# emg-bridge.net
KiCad netlist of a schematic drawn in EAGLE
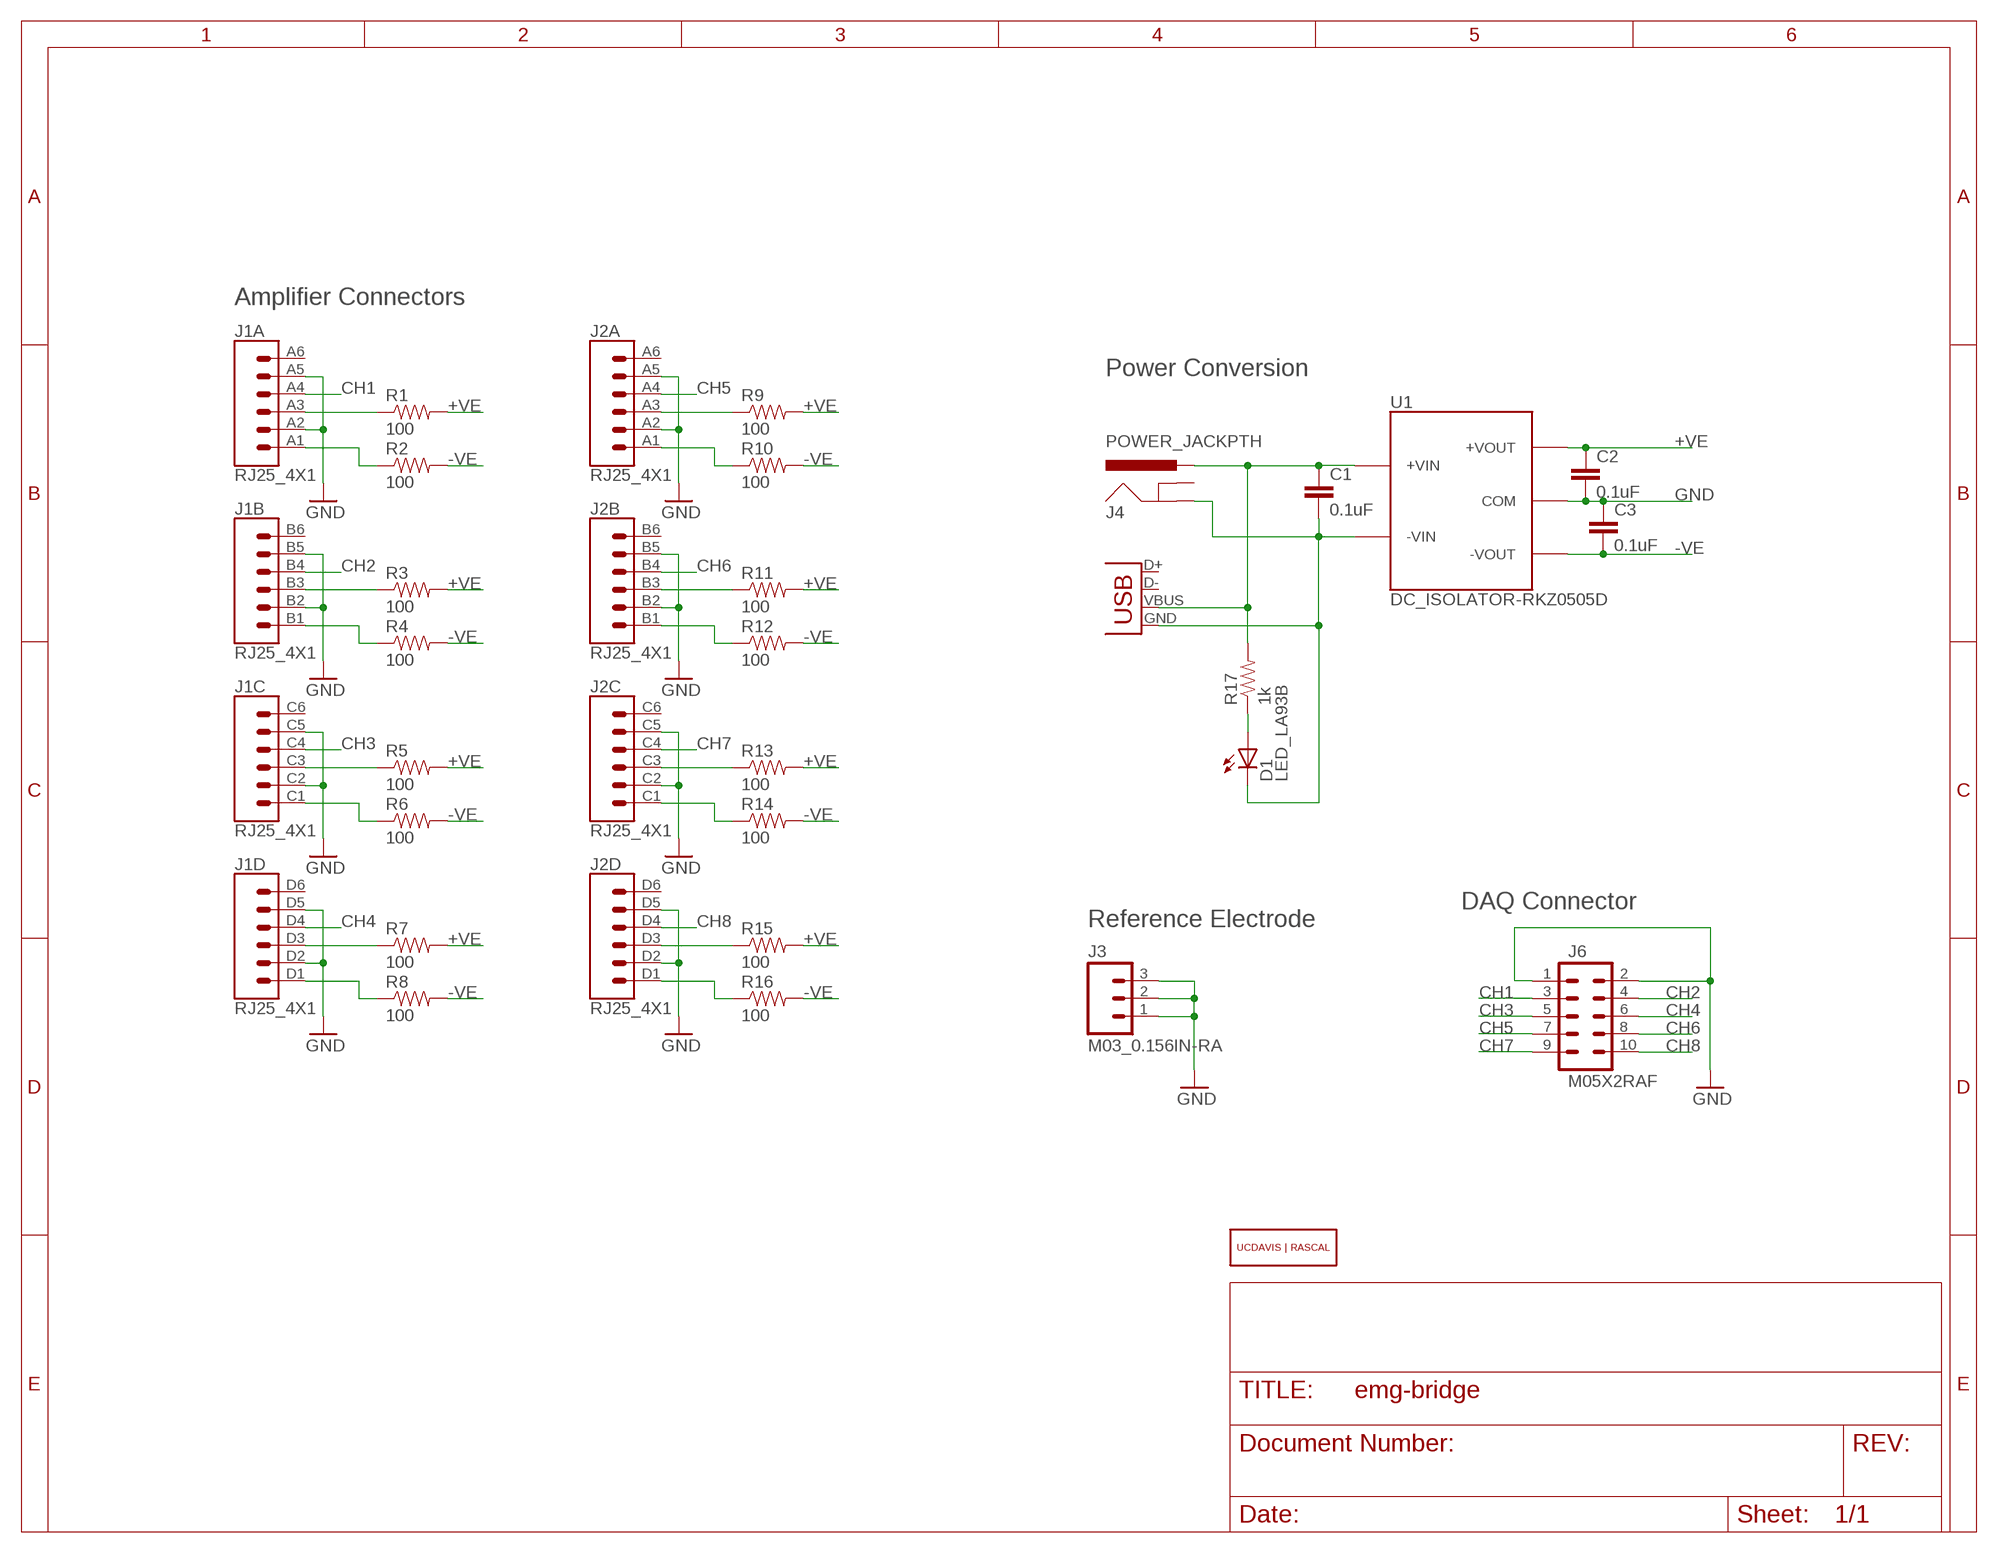
[diagram p0: schematic, sheet 1]

(export (version "E")
  (design (tool "Eeschema 10.0.6"))
  (components
    (comp (ref "C1")
      (value "0.1uF")
      (footprint "eagle-import:0805")
      (libsource (lib "eagle-import") (part "CAP0805"))
    )
    (comp (ref "C2")
      (value "0.1uF")
      (footprint "eagle-import:0805")
      (libsource (lib "eagle-import") (part "CAP0805"))
    )
    (comp (ref "C3")
      (value "0.1uF")
      (footprint "eagle-import:0805")
      (libsource (lib "eagle-import") (part "CAP0805"))
    )
    (comp (ref "D1")
      (value "LED_LA93B")
      (footprint "eagle-import:LED_RA")
      (libsource (lib "eagle-import") (part "LED_LA93B"))
    )
    (comp (ref "J1")
      (value "RJ25_4X1")
      (footprint "eagle-import:RJ25_4X1")
      (libsource (lib "eagle-import") (part "RJ25_4X1"))
    )
    (comp (ref "J2")
      (value "RJ25_4X1")
      (footprint "eagle-import:RJ25_4X1")
      (libsource (lib "eagle-import") (part "RJ25_4X1"))
    )
    (comp (ref "J3")
      (value "M03_0.156IN-RA")
      (footprint "eagle-import:TE_640389-3")
      (libsource (lib "eagle-import") (part "M03_0.156IN-RA"))
    )
    (comp (ref "J4")
      (value "POWER_JACKPTH")
      (footprint "eagle-import:POWER_JACK_PTH")
      (libsource (lib "eagle-import") (part "POWER_JACKPTH"))
    )
    (comp (ref "J5")
      (value "USB-B")
      (footprint "eagle-import:USB-B-PTH")
      (libsource (lib "eagle-import") (part "USBPTH"))
    )
    (comp (ref "J6")
      (value "M05X2RAF")
      (footprint "eagle-import:2X5-RAF")
      (libsource (lib "eagle-import") (part "M05X2RAF"))
    )
    (comp (ref "R1")
      (value "100")
      (footprint "eagle-import:0805")
      (libsource (lib "eagle-import") (part "RESISTOR0805-RES"))
    )
    (comp (ref "R2")
      (value "100")
      (footprint "eagle-import:0805")
      (libsource (lib "eagle-import") (part "RESISTOR0805-RES"))
    )
    (comp (ref "R3")
      (value "100")
      (footprint "eagle-import:0805")
      (libsource (lib "eagle-import") (part "RESISTOR0805-RES"))
    )
    (comp (ref "R4")
      (value "100")
      (footprint "eagle-import:0805")
      (libsource (lib "eagle-import") (part "RESISTOR0805-RES"))
    )
    (comp (ref "R5")
      (value "100")
      (footprint "eagle-import:0805")
      (libsource (lib "eagle-import") (part "RESISTOR0805-RES"))
    )
    (comp (ref "R6")
      (value "100")
      (footprint "eagle-import:0805")
      (libsource (lib "eagle-import") (part "RESISTOR0805-RES"))
    )
    (comp (ref "R7")
      (value "100")
      (footprint "eagle-import:0805")
      (libsource (lib "eagle-import") (part "RESISTOR0805-RES"))
    )
    (comp (ref "R8")
      (value "100")
      (footprint "eagle-import:0805")
      (libsource (lib "eagle-import") (part "RESISTOR0805-RES"))
    )
    (comp (ref "R9")
      (value "100")
      (footprint "eagle-import:0805")
      (libsource (lib "eagle-import") (part "RESISTOR0805-RES"))
    )
    (comp (ref "R10")
      (value "100")
      (footprint "eagle-import:0805")
      (libsource (lib "eagle-import") (part "RESISTOR0805-RES"))
    )
    (comp (ref "R11")
      (value "100")
      (footprint "eagle-import:0805")
      (libsource (lib "eagle-import") (part "RESISTOR0805-RES"))
    )
    (comp (ref "R12")
      (value "100")
      (footprint "eagle-import:0805")
      (libsource (lib "eagle-import") (part "RESISTOR0805-RES"))
    )
    (comp (ref "R13")
      (value "100")
      (footprint "eagle-import:0805")
      (libsource (lib "eagle-import") (part "RESISTOR0805-RES"))
    )
    (comp (ref "R14")
      (value "100")
      (footprint "eagle-import:0805")
      (libsource (lib "eagle-import") (part "RESISTOR0805-RES"))
    )
    (comp (ref "R15")
      (value "100")
      (footprint "eagle-import:0805")
      (libsource (lib "eagle-import") (part "RESISTOR0805-RES"))
    )
    (comp (ref "R16")
      (value "100")
      (footprint "eagle-import:0805")
      (libsource (lib "eagle-import") (part "RESISTOR0805-RES"))
    )
    (comp (ref "R17")
      (value "1k")
      (footprint "eagle-import:0805")
      (libsource (lib "eagle-import") (part "RESISTOR0805-RES"))
    )
    (comp (ref "U$1")
      (value "UCDAVIS-RASCAL_LOGO-2LINE")
      (footprint "eagle-import:UCDAVIS-RASCAL_LOGO")
      (libsource (lib "eagle-import") (part "UCDAVIS-RASCAL_LOGO-2LINE"))
    )
    (comp (ref "U1")
      (value "DC_ISOLATOR-RKZ0505D")
      (footprint "eagle-import:SIP7")
      (libsource (lib "eagle-import") (part "DC_ISOLATOR-RKZ0505D"))
    )
  )
  (nets
    (net (code "1") (name "/+VE") (class "Default")
      (node (ref "C2") (pin "1") (pinfunction "1_1") (pintype "passive"))
      (node (ref "R1") (pin "2") (pinfunction "2_2") (pintype "passive"))
      (node (ref "R11") (pin "2") (pinfunction "2_2") (pintype "passive"))
      (node (ref "R13") (pin "2") (pinfunction "2_2") (pintype "passive"))
      (node (ref "R15") (pin "2") (pinfunction "2_2") (pintype "passive"))
      (node (ref "R3") (pin "2") (pinfunction "2_2") (pintype "passive"))
      (node (ref "R5") (pin "2") (pinfunction "2_2") (pintype "passive"))
      (node (ref "R7") (pin "2") (pinfunction "2_2") (pintype "passive"))
      (node (ref "R9") (pin "2") (pinfunction "2_2") (pintype "passive"))
      (node (ref "U1") (pin "7") (pinfunction "+VOUT_7") (pintype "bidirectional"))
    )
    (net (code "2") (name "/-VE") (class "Default")
      (node (ref "C3") (pin "2") (pinfunction "2_2") (pintype "passive"))
      (node (ref "R10") (pin "2") (pinfunction "2_2") (pintype "passive"))
      (node (ref "R12") (pin "2") (pinfunction "2_2") (pintype "passive"))
      (node (ref "R14") (pin "2") (pinfunction "2_2") (pintype "passive"))
      (node (ref "R16") (pin "2") (pinfunction "2_2") (pintype "passive"))
      (node (ref "R2") (pin "2") (pinfunction "2_2") (pintype "passive"))
      (node (ref "R4") (pin "2") (pinfunction "2_2") (pintype "passive"))
      (node (ref "R6") (pin "2") (pinfunction "2_2") (pintype "passive"))
      (node (ref "R8") (pin "2") (pinfunction "2_2") (pintype "passive"))
      (node (ref "U1") (pin "5") (pinfunction "-VOUT_5") (pintype "bidirectional"))
    )
    (net (code "3") (name "/CH1") (class "Default")
      (node (ref "J1") (pin "A4") (pinfunction "P$4_A4") (pintype "bidirectional"))
      (node (ref "J6") (pin "3") (pinfunction "3_3") (pintype "passive"))
    )
    (net (code "4") (name "/CH2") (class "Default")
      (node (ref "J1") (pin "B4") (pinfunction "P$4_B4") (pintype "bidirectional"))
      (node (ref "J6") (pin "4") (pinfunction "4_4") (pintype "passive"))
    )
    (net (code "5") (name "/CH3") (class "Default")
      (node (ref "J1") (pin "C4") (pinfunction "P$4_C4") (pintype "bidirectional"))
      (node (ref "J6") (pin "5") (pinfunction "5_5") (pintype "passive"))
    )
    (net (code "6") (name "/CH4") (class "Default")
      (node (ref "J1") (pin "D4") (pinfunction "P$4_D4") (pintype "bidirectional"))
      (node (ref "J6") (pin "6") (pinfunction "6_6") (pintype "passive"))
    )
    (net (code "7") (name "/CH5") (class "Default")
      (node (ref "J2") (pin "A4") (pinfunction "P$4_A4") (pintype "bidirectional"))
      (node (ref "J6") (pin "7") (pinfunction "7_7") (pintype "passive"))
    )
    (net (code "8") (name "/CH6") (class "Default")
      (node (ref "J2") (pin "B4") (pinfunction "P$4_B4") (pintype "bidirectional"))
      (node (ref "J6") (pin "8") (pinfunction "8_8") (pintype "passive"))
    )
    (net (code "9") (name "/CH7") (class "Default")
      (node (ref "J2") (pin "C4") (pinfunction "P$4_C4") (pintype "bidirectional"))
      (node (ref "J6") (pin "9") (pinfunction "9_9") (pintype "passive"))
    )
    (net (code "10") (name "/CH8") (class "Default")
      (node (ref "J2") (pin "D4") (pinfunction "P$4_D4") (pintype "bidirectional"))
      (node (ref "J6") (pin "10") (pinfunction "10_10") (pintype "passive"))
    )
    (net (code "11") (name "GND") (class "Default")
      (node (ref "C2") (pin "2") (pinfunction "2_2") (pintype "passive"))
      (node (ref "C3") (pin "1") (pinfunction "1_1") (pintype "passive"))
      (node (ref "J1") (pin "A2") (pinfunction "P$2_A2") (pintype "bidirectional"))
      (node (ref "J1") (pin "A5") (pinfunction "P$5_A5") (pintype "bidirectional"))
      (node (ref "J1") (pin "B2") (pinfunction "P$2_B2") (pintype "bidirectional"))
      (node (ref "J1") (pin "B5") (pinfunction "P$5_B5") (pintype "bidirectional"))
      (node (ref "J1") (pin "C2") (pinfunction "P$2_C2") (pintype "bidirectional"))
      (node (ref "J1") (pin "C5") (pinfunction "P$5_C5") (pintype "bidirectional"))
      (node (ref "J1") (pin "D2") (pinfunction "P$2_D2") (pintype "bidirectional"))
      (node (ref "J1") (pin "D5") (pinfunction "P$5_D5") (pintype "bidirectional"))
      (node (ref "J2") (pin "A2") (pinfunction "P$2_A2") (pintype "bidirectional"))
      (node (ref "J2") (pin "A5") (pinfunction "P$5_A5") (pintype "bidirectional"))
      (node (ref "J2") (pin "B2") (pinfunction "P$2_B2") (pintype "bidirectional"))
      (node (ref "J2") (pin "B5") (pinfunction "P$5_B5") (pintype "bidirectional"))
      (node (ref "J2") (pin "C2") (pinfunction "P$2_C2") (pintype "bidirectional"))
      (node (ref "J2") (pin "C5") (pinfunction "P$5_C5") (pintype "bidirectional"))
      (node (ref "J2") (pin "D2") (pinfunction "P$2_D2") (pintype "bidirectional"))
      (node (ref "J2") (pin "D5") (pinfunction "P$5_D5") (pintype "bidirectional"))
      (node (ref "J3") (pin "1") (pinfunction "1_1") (pintype "passive"))
      (node (ref "J3") (pin "2") (pinfunction "2_2") (pintype "passive"))
      (node (ref "J3") (pin "3") (pinfunction "3_3") (pintype "passive"))
      (node (ref "J6") (pin "1") (pinfunction "1_1") (pintype "passive"))
      (node (ref "J6") (pin "2") (pinfunction "2_2") (pintype "passive"))
      (node (ref "U1") (pin "6") (pinfunction "COM_6") (pintype "bidirectional"))
    )
    (net (code "12") (name "Net-(D1-C)") (class "Default")
      (node (ref "C1") (pin "2") (pinfunction "2_2") (pintype "passive"))
      (node (ref "D1") (pin "K") (pinfunction "C_K") (pintype "passive"))
      (node (ref "J4") (pin "GND") (pinfunction "GND_GND") (pintype "bidirectional"))
      (node (ref "J5") (pin "GND") (pinfunction "GND_GND") (pintype "bidirectional"))
      (node (ref "U1") (pin "2") (pinfunction "-VIN_2") (pintype "bidirectional"))
    )
    (net (code "13") (name "Net-(D1-PadA)") (class "Default")
      (node (ref "D1") (pin "A") (pinfunction "A_A") (pintype "passive"))
      (node (ref "R17") (pin "1") (pinfunction "1_1") (pintype "passive"))
    )
    (net (code "14") (name "Net-(J1A-P$1)") (class "Default")
      (node (ref "J1") (pin "A1") (pinfunction "P$1_A1") (pintype "bidirectional"))
      (node (ref "R2") (pin "1") (pinfunction "1_1") (pintype "passive"))
    )
    (net (code "15") (name "Net-(J1A-P$3)") (class "Default")
      (node (ref "J1") (pin "A3") (pinfunction "P$3_A3") (pintype "bidirectional"))
      (node (ref "R1") (pin "1") (pinfunction "1_1") (pintype "passive"))
    )
    (net (code "16") (name "Net-(J1B-P$1)") (class "Default")
      (node (ref "J1") (pin "B1") (pinfunction "P$1_B1") (pintype "bidirectional"))
      (node (ref "R4") (pin "1") (pinfunction "1_1") (pintype "passive"))
    )
    (net (code "17") (name "Net-(J1B-P$3)") (class "Default")
      (node (ref "J1") (pin "B3") (pinfunction "P$3_B3") (pintype "bidirectional"))
      (node (ref "R3") (pin "1") (pinfunction "1_1") (pintype "passive"))
    )
    (net (code "18") (name "Net-(J1C-P$1)") (class "Default")
      (node (ref "J1") (pin "C1") (pinfunction "P$1_C1") (pintype "bidirectional"))
      (node (ref "R6") (pin "1") (pinfunction "1_1") (pintype "passive"))
    )
    (net (code "19") (name "Net-(J1C-P$3)") (class "Default")
      (node (ref "J1") (pin "C3") (pinfunction "P$3_C3") (pintype "bidirectional"))
      (node (ref "R5") (pin "1") (pinfunction "1_1") (pintype "passive"))
    )
    (net (code "20") (name "Net-(J1D-P$1)") (class "Default")
      (node (ref "J1") (pin "D1") (pinfunction "P$1_D1") (pintype "bidirectional"))
      (node (ref "R8") (pin "1") (pinfunction "1_1") (pintype "passive"))
    )
    (net (code "21") (name "Net-(J1D-P$3)") (class "Default")
      (node (ref "J1") (pin "D3") (pinfunction "P$3_D3") (pintype "bidirectional"))
      (node (ref "R7") (pin "1") (pinfunction "1_1") (pintype "passive"))
    )
    (net (code "22") (name "Net-(J2A-P$1)") (class "Default")
      (node (ref "J2") (pin "A1") (pinfunction "P$1_A1") (pintype "bidirectional"))
      (node (ref "R10") (pin "1") (pinfunction "1_1") (pintype "passive"))
    )
    (net (code "23") (name "Net-(J2A-P$3)") (class "Default")
      (node (ref "J2") (pin "A3") (pinfunction "P$3_A3") (pintype "bidirectional"))
      (node (ref "R9") (pin "1") (pinfunction "1_1") (pintype "passive"))
    )
    (net (code "24") (name "Net-(J2B-P$1)") (class "Default")
      (node (ref "J2") (pin "B1") (pinfunction "P$1_B1") (pintype "bidirectional"))
      (node (ref "R12") (pin "1") (pinfunction "1_1") (pintype "passive"))
    )
    (net (code "25") (name "Net-(J2B-P$3)") (class "Default")
      (node (ref "J2") (pin "B3") (pinfunction "P$3_B3") (pintype "bidirectional"))
      (node (ref "R11") (pin "1") (pinfunction "1_1") (pintype "passive"))
    )
    (net (code "26") (name "Net-(J2C-P$1)") (class "Default")
      (node (ref "J2") (pin "C1") (pinfunction "P$1_C1") (pintype "bidirectional"))
      (node (ref "R14") (pin "1") (pinfunction "1_1") (pintype "passive"))
    )
    (net (code "27") (name "Net-(J2C-P$3)") (class "Default")
      (node (ref "J2") (pin "C3") (pinfunction "P$3_C3") (pintype "bidirectional"))
      (node (ref "R13") (pin "1") (pinfunction "1_1") (pintype "passive"))
    )
    (net (code "28") (name "Net-(J2D-P$1)") (class "Default")
      (node (ref "J2") (pin "D1") (pinfunction "P$1_D1") (pintype "bidirectional"))
      (node (ref "R16") (pin "1") (pinfunction "1_1") (pintype "passive"))
    )
    (net (code "29") (name "Net-(J2D-P$3)") (class "Default")
      (node (ref "J2") (pin "D3") (pinfunction "P$3_D3") (pintype "bidirectional"))
      (node (ref "R15") (pin "1") (pinfunction "1_1") (pintype "passive"))
    )
    (net (code "30") (name "Net-(U1-+VIN)") (class "Default")
      (node (ref "C1") (pin "1") (pinfunction "1_1") (pintype "passive"))
      (node (ref "J4") (pin "PWR") (pinfunction "PWR_PWR") (pintype "bidirectional"))
      (node (ref "J5") (pin "VBUS") (pinfunction "VBUS_VBUS") (pintype "bidirectional"))
      (node (ref "R17") (pin "2") (pinfunction "2_2") (pintype "passive"))
      (node (ref "U1") (pin "1") (pinfunction "+VIN_1") (pintype "bidirectional"))
    )
    (net (code "31") (name "unconnected-(J1A-P$6-PadA6)") (class "Default")
      (node (ref "J1") (pin "A6") (pinfunction "P$6_A6") (pintype "bidirectional"))
    )
    (net (code "32") (name "unconnected-(J1B-P$6-PadB6)") (class "Default")
      (node (ref "J1") (pin "B6") (pinfunction "P$6_B6") (pintype "bidirectional"))
    )
    (net (code "33") (name "unconnected-(J1C-P$6-PadC6)") (class "Default")
      (node (ref "J1") (pin "C6") (pinfunction "P$6_C6") (pintype "bidirectional"))
    )
    (net (code "34") (name "unconnected-(J1D-P$6-PadD6)") (class "Default")
      (node (ref "J1") (pin "D6") (pinfunction "P$6_D6") (pintype "bidirectional"))
    )
    (net (code "35") (name "unconnected-(J2A-P$6-PadA6)") (class "Default")
      (node (ref "J2") (pin "A6") (pinfunction "P$6_A6") (pintype "bidirectional"))
    )
    (net (code "36") (name "unconnected-(J2B-P$6-PadB6)") (class "Default")
      (node (ref "J2") (pin "B6") (pinfunction "P$6_B6") (pintype "bidirectional"))
    )
    (net (code "37") (name "unconnected-(J2C-P$6-PadC6)") (class "Default")
      (node (ref "J2") (pin "C6") (pinfunction "P$6_C6") (pintype "bidirectional"))
    )
    (net (code "38") (name "unconnected-(J2D-P$6-PadD6)") (class "Default")
      (node (ref "J2") (pin "D6") (pinfunction "P$6_D6") (pintype "bidirectional"))
    )
    (net (code "39") (name "unconnected-(J4-PadGNDBREAK)") (class "Default")
      (node (ref "J4") (pin "GNDBREAK") (pinfunction "GNDBREAK_GNDBREAK") (pintype "bidirectional"))
    )
    (net (code "40") (name "unconnected-(J5-PadD+)") (class "Default")
      (node (ref "J5") (pin "D+") (pinfunction "D+_D+") (pintype "bidirectional"))
    )
    (net (code "41") (name "unconnected-(J5-PadD-)") (class "Default")
      (node (ref "J5") (pin "D-") (pinfunction "D-_D-") (pintype "bidirectional"))
    )
  )
)
